# Flight_control_Prototipe.net
KiCad netlist of a schematic drawn in EAGLE
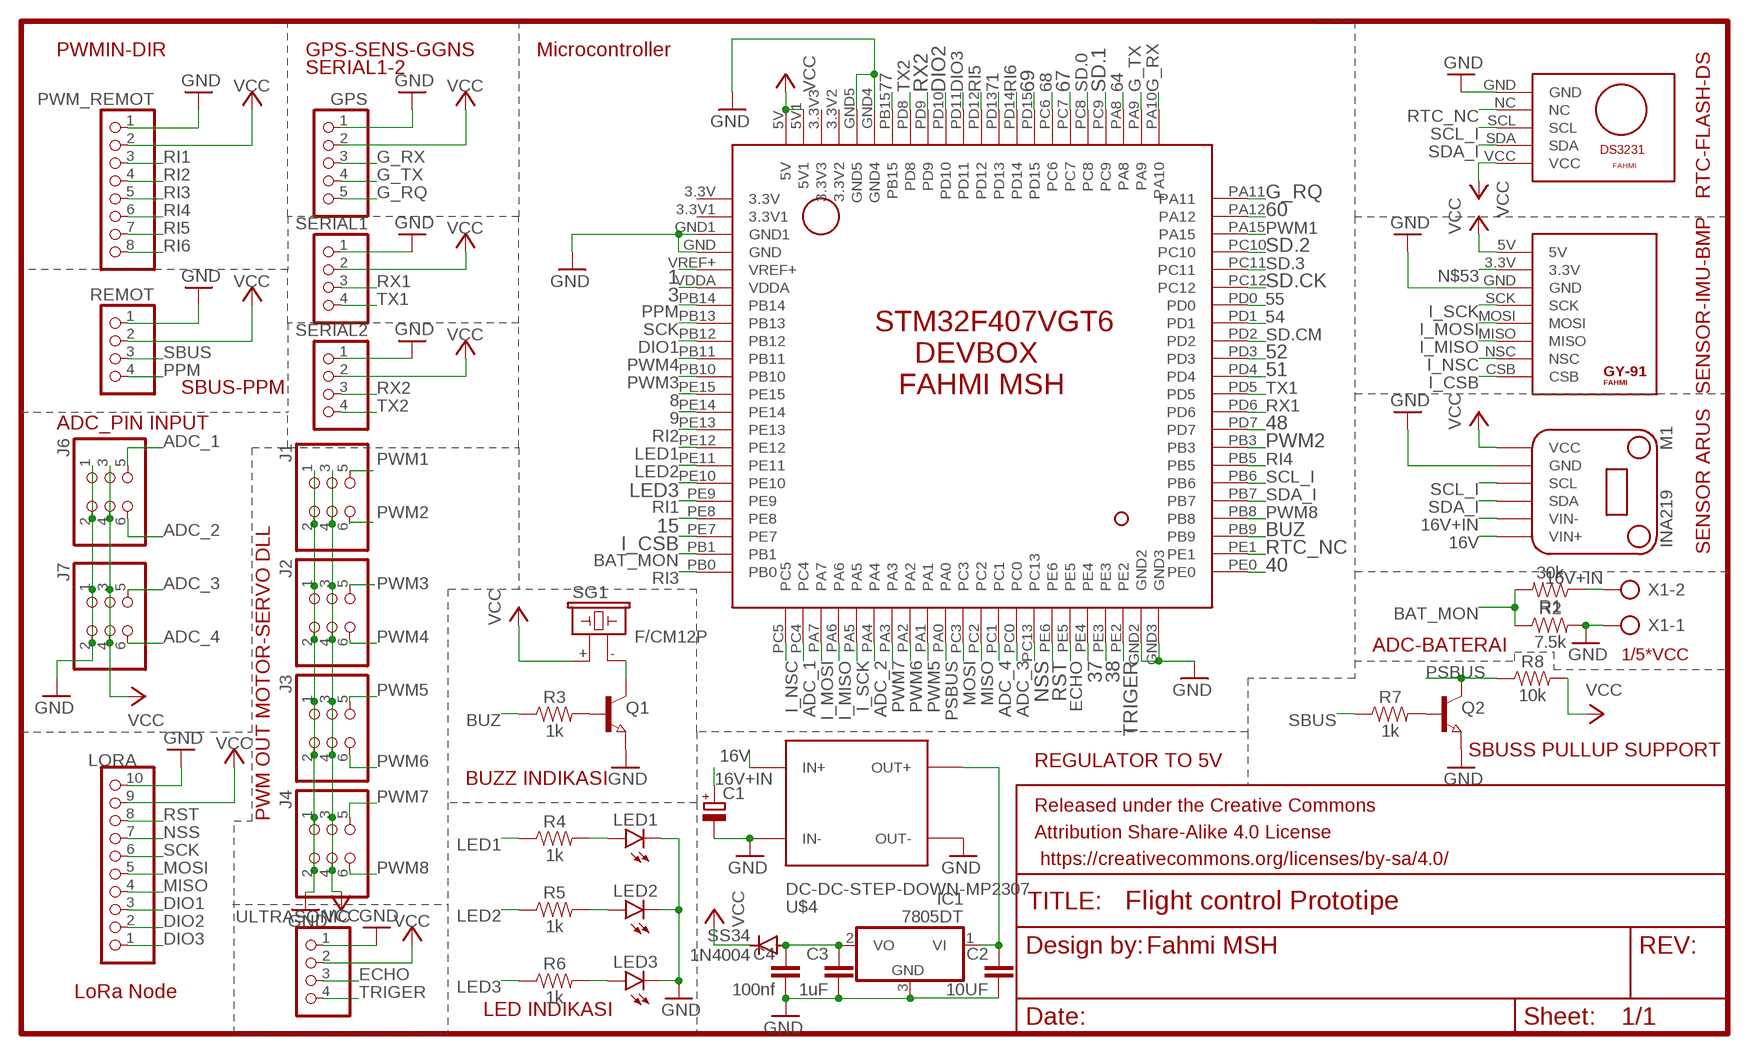
[diagram p0: schematic, sheet 1]

(export (version "E")
  (design (tool "Eeschema 10.0.6"))
  (components
    (comp (ref "C1")
      (value "CPOL-EUE3.5-8")
      (footprint "eagle-import:E3,5-8")
      (libsource (lib "eagle-import") (part "CPOL-EUE3.5-8"))
    )
    (comp (ref "C2")
      (value "10UF")
      (footprint "eagle-import:C0805K")
      (libsource (lib "eagle-import") (part "C-EUC0805K"))
    )
    (comp (ref "C3")
      (value "1uF")
      (footprint "eagle-import:C0805K")
      (libsource (lib "eagle-import") (part "C-EUC0805K"))
    )
    (comp (ref "C4")
      (value "100nf")
      (footprint "eagle-import:C0805K")
      (libsource (lib "eagle-import") (part "C-EUC0805K"))
    )
    (comp (ref "FRAME1")
      (value "FRAME-LEDGER")
      (footprint "eagle-import:CREATIVE_COMMONS")
      (libsource (lib "eagle-import") (part "FRAME-LEDGER"))
    )
    (comp (ref "GPS")
      (value "PINHD-1X5")
      (footprint "eagle-import:1X05")
      (libsource (lib "eagle-import") (part "PINHD-1X5"))
    )
    (comp (ref "IC1")
      (value "7805DT")
      (footprint "eagle-import:TO252")
      (libsource (lib "eagle-import") (part "78DT05"))
    )
    (comp (ref "J1")
      (value "PINHD-2X3")
      (footprint "eagle-import:2X03")
      (libsource (lib "eagle-import") (part "PINHD-2X3"))
    )
    (comp (ref "J2")
      (value "PINHD-2X3")
      (footprint "eagle-import:2X03")
      (libsource (lib "eagle-import") (part "PINHD-2X3"))
    )
    (comp (ref "J3")
      (value "PINHD-2X3")
      (footprint "eagle-import:2X03")
      (libsource (lib "eagle-import") (part "PINHD-2X3"))
    )
    (comp (ref "J4")
      (value "PINHD-2X3")
      (footprint "eagle-import:2X03")
      (libsource (lib "eagle-import") (part "PINHD-2X3"))
    )
    (comp (ref "J6")
      (value "PINHD-2X3")
      (footprint "eagle-import:2X03")
      (libsource (lib "eagle-import") (part "PINHD-2X3"))
    )
    (comp (ref "J7")
      (value "PINHD-2X3")
      (footprint "eagle-import:2X03")
      (libsource (lib "eagle-import") (part "PINHD-2X3"))
    )
    (comp (ref "LED1")
      (value "LED3MM")
      (footprint "eagle-import:LED3MM")
      (libsource (lib "eagle-import") (part "LED3MM"))
    )
    (comp (ref "LED2")
      (value "LED3MM")
      (footprint "eagle-import:LED3MM")
      (libsource (lib "eagle-import") (part "LED3MM"))
    )
    (comp (ref "LED3")
      (value "LED3MM")
      (footprint "eagle-import:LED3MM")
      (libsource (lib "eagle-import") (part "LED3MM"))
    )
    (comp (ref "LORA")
      (value "PINHD-1X10")
      (footprint "eagle-import:1X10")
      (libsource (lib "eagle-import") (part "PINHD-1X10"))
    )
    (comp (ref "M1")
      (value "INA219")
      (footprint "eagle-import:INA219")
      (libsource (lib "eagle-import") (part "INA219"))
    )
    (comp (ref "PWM_REMOT")
      (value "PINHD-1X8")
      (footprint "eagle-import:1X08")
      (libsource (lib "eagle-import") (part "PINHD-1X8"))
    )
    (comp (ref "Q1")
      (value "NPN-TRANSISTOR_SOT23")
      (footprint "eagle-import:SOT23")
      (libsource (lib "eagle-import") (part "NPN-TRANSISTOR_SOT23"))
    )
    (comp (ref "Q2")
      (value "NPN-TRANSISTOR_SOT23")
      (footprint "eagle-import:SOT23")
      (libsource (lib "eagle-import") (part "NPN-TRANSISTOR_SOT23"))
    )
    (comp (ref "R1")
      (value "30k")
      (footprint "eagle-import:0805")
      (libsource (lib "eagle-import") (part "0.75OHM-0805-1/4W-1%"))
    )
    (comp (ref "R2")
      (value "7.5k")
      (footprint "eagle-import:0805")
      (libsource (lib "eagle-import") (part "0.75OHM-0805-1/4W-1%"))
    )
    (comp (ref "R3")
      (value "1k")
      (footprint "eagle-import:0805")
      (libsource (lib "eagle-import") (part "0.75OHM-0805-1/4W-1%"))
    )
    (comp (ref "R4")
      (value "1k")
      (footprint "eagle-import:0805")
      (libsource (lib "eagle-import") (part "0.75OHM-0805-1/4W-1%"))
    )
    (comp (ref "R5")
      (value "1k")
      (footprint "eagle-import:0805")
      (libsource (lib "eagle-import") (part "0.75OHM-0805-1/4W-1%"))
    )
    (comp (ref "R6")
      (value "1k")
      (footprint "eagle-import:0805")
      (libsource (lib "eagle-import") (part "0.75OHM-0805-1/4W-1%"))
    )
    (comp (ref "R7")
      (value "1k")
      (footprint "eagle-import:0805")
      (libsource (lib "eagle-import") (part "0.75OHM-0805-1/4W-1%"))
    )
    (comp (ref "R8")
      (value "10k")
      (footprint "eagle-import:0805")
      (libsource (lib "eagle-import") (part "0.75OHM-0805-1/4W-1%"))
    )
    (comp (ref "REMOT")
      (value "PINHD-1X4")
      (footprint "eagle-import:1X04")
      (libsource (lib "eagle-import") (part "PINHD-1X4"))
    )
    (comp (ref "SERIAL1")
      (value "PINHD-1X4")
      (footprint "eagle-import:1X04")
      (libsource (lib "eagle-import") (part "PINHD-1X4"))
    )
    (comp (ref "SERIAL2")
      (value "PINHD-1X4")
      (footprint "eagle-import:1X04")
      (libsource (lib "eagle-import") (part "PINHD-1X4"))
    )
    (comp (ref "SG1")
      (value "F/CM12P")
      (footprint "eagle-import:F_CM12P")
      (libsource (lib "eagle-import") (part "F/CM12P"))
    )
    (comp (ref "SS34")
      (value "1N4004")
      (footprint "eagle-import:DO41-10")
      (libsource (lib "eagle-import") (part "1N4004"))
    )
    (comp (ref "U$1")
      (value "STM32F4DEVBOX")
      (footprint "eagle-import:STM32F4DEVBOX")
      (libsource (lib "eagle-import") (part "STM32F4DEVBOX"))
    )
    (comp (ref "U$2")
      (value "GY-91")
      (footprint "eagle-import:GY-91")
      (libsource (lib "eagle-import") (part "GY-91"))
    )
    (comp (ref "U$3")
      (value "DS3231MINI")
      (footprint "eagle-import:DS3231MINI")
      (libsource (lib "eagle-import") (part "DS3231MINI"))
    )
    (comp (ref "U$4")
      (value "DC-DC-STEP-DOWN-MP2307")
      (footprint "eagle-import:DC-DC-STEP-DOWN-MP2307")
      (libsource (lib "eagle-import") (part "DC-DC-STEP-DOWN-MP2307"))
    )
    (comp (ref "ULTRASONIC")
      (value "PINHD-1X4")
      (footprint "eagle-import:1X04")
      (libsource (lib "eagle-import") (part "PINHD-1X4"))
    )
    (comp (ref "X1")
      (value "AK500/2")
      (footprint "eagle-import:AK500_2")
      (libsource (lib "eagle-import") (part "AK500/2"))
    )
  )
  (nets
    (net (code "1") (name "/1") (class "Default")
      (node (ref "U$1") (pin "VREF+") (pinfunction "VREF+_VREF+") (pintype "bidirectional"))
    )
    (net (code "2") (name "/3") (class "Default")
      (node (ref "U$1") (pin "VDDA") (pinfunction "VDDA_VDDA") (pintype "bidirectional"))
    )
    (net (code "3") (name "/8") (class "Default")
      (node (ref "U$1") (pin "PE15") (pinfunction "PE15_PE15") (pintype "bidirectional"))
    )
    (net (code "4") (name "/9") (class "Default")
      (node (ref "U$1") (pin "PE14") (pinfunction "PE14_PE14") (pintype "bidirectional"))
    )
    (net (code "5") (name "/15") (class "Default")
      (node (ref "U$1") (pin "PE8") (pinfunction "PE8_PE8") (pintype "bidirectional"))
    )
    (net (code "6") (name "/16V") (class "Default")
      (node (ref "M1") (pin "VIN+") (pinfunction "VIN+_VIN+") (pintype "bidirectional"))
      (node (ref "U$4") (pin "IN+") (pinfunction "IN+_IN+") (pintype "bidirectional"))
    )
    (net (code "7") (name "/16V+IN") (class "Default")
      (node (ref "C1") (pin "+") (pinfunction "+_+") (pintype "passive"))
      (node (ref "M1") (pin "VIN-") (pinfunction "VIN-_VIN-") (pintype "bidirectional"))
      (node (ref "R1") (pin "1") (pinfunction "1_1") (pintype "passive"))
      (node (ref "X1") (pin "2") (pinfunction "KL_2") (pintype "passive"))
    )
    (net (code "8") (name "/37") (class "Default")
      (node (ref "U$1") (pin "PE4") (pinfunction "PE4_PE4") (pintype "bidirectional"))
    )
    (net (code "9") (name "/38") (class "Default")
      (node (ref "U$1") (pin "PE3") (pinfunction "PE3_PE3") (pintype "bidirectional"))
    )
    (net (code "10") (name "/40") (class "Default")
      (node (ref "U$1") (pin "PE0") (pinfunction "PE0_PE0") (pintype "bidirectional"))
    )
    (net (code "11") (name "/48") (class "Default")
      (node (ref "U$1") (pin "PD7") (pinfunction "PD7_PD7") (pintype "bidirectional"))
    )
    (net (code "12") (name "/51") (class "Default")
      (node (ref "U$1") (pin "PD4") (pinfunction "PD4_PD4") (pintype "bidirectional"))
    )
    (net (code "13") (name "/52") (class "Default")
      (node (ref "U$1") (pin "PD3") (pinfunction "PD3_PD3") (pintype "bidirectional"))
    )
    (net (code "14") (name "/54") (class "Default")
      (node (ref "U$1") (pin "PD1") (pinfunction "PD1_PD1") (pintype "bidirectional"))
    )
    (net (code "15") (name "/55") (class "Default")
      (node (ref "U$1") (pin "PD0") (pinfunction "PD0_PD0") (pintype "bidirectional"))
    )
    (net (code "16") (name "/60") (class "Default")
      (node (ref "U$1") (pin "PA12") (pinfunction "PA12_PA12") (pintype "bidirectional"))
    )
    (net (code "17") (name "/64") (class "Default")
      (node (ref "U$1") (pin "PA8") (pinfunction "PA8_PA8") (pintype "bidirectional"))
    )
    (net (code "18") (name "/67") (class "Default")
      (node (ref "U$1") (pin "PC7") (pinfunction "PC7_PC7") (pintype "bidirectional"))
    )
    (net (code "19") (name "/68") (class "Default")
      (node (ref "U$1") (pin "PC6") (pinfunction "PC6_PC6") (pintype "bidirectional"))
    )
    (net (code "20") (name "/69") (class "Default")
      (node (ref "U$1") (pin "PD15") (pinfunction "PD15_PD15") (pintype "bidirectional"))
    )
    (net (code "21") (name "/71") (class "Default")
      (node (ref "U$1") (pin "PD13") (pinfunction "PD13_PD13") (pintype "bidirectional"))
    )
    (net (code "22") (name "/77") (class "Default")
      (node (ref "U$1") (pin "PB15") (pinfunction "PB15_PB15") (pintype "bidirectional"))
    )
    (net (code "23") (name "/ADC_1") (class "Default")
      (node (ref "J6") (pin "5") (pinfunction "5_5") (pintype "passive"))
      (node (ref "U$1") (pin "PC4") (pinfunction "PC4_PC4") (pintype "bidirectional"))
    )
    (net (code "24") (name "/ADC_2") (class "Default")
      (node (ref "J6") (pin "6") (pinfunction "6_6") (pintype "passive"))
      (node (ref "U$1") (pin "PA4") (pinfunction "PA4_PA4") (pintype "bidirectional"))
    )
    (net (code "25") (name "/ADC_3") (class "Default")
      (node (ref "J7") (pin "5") (pinfunction "5_5") (pintype "passive"))
      (node (ref "U$1") (pin "PC0") (pinfunction "PC0_PC0") (pintype "bidirectional"))
    )
    (net (code "26") (name "/ADC_4") (class "Default")
      (node (ref "J7") (pin "6") (pinfunction "6_6") (pintype "passive"))
      (node (ref "U$1") (pin "PC1") (pinfunction "PC1_PC1") (pintype "bidirectional"))
    )
    (net (code "27") (name "/BAT_MON") (class "Default")
      (node (ref "R1") (pin "2") (pinfunction "2_2") (pintype "passive"))
      (node (ref "R2") (pin "1") (pinfunction "1_1") (pintype "passive"))
      (node (ref "U$1") (pin "PB1") (pinfunction "PB1_PB1") (pintype "bidirectional"))
    )
    (net (code "28") (name "/BUZ") (class "Default")
      (node (ref "R3") (pin "1") (pinfunction "1_1") (pintype "passive"))
      (node (ref "U$1") (pin "PB9") (pinfunction "PB9_PB9") (pintype "bidirectional"))
    )
    (net (code "29") (name "/DIO1") (class "Default")
      (node (ref "LORA") (pin "3") (pinfunction "3_3") (pintype "passive"))
      (node (ref "U$1") (pin "PB12") (pinfunction "PB12_PB12") (pintype "bidirectional"))
    )
    (net (code "30") (name "/DIO2") (class "Default")
      (node (ref "LORA") (pin "2") (pinfunction "2_2") (pintype "passive"))
      (node (ref "U$1") (pin "PD10") (pinfunction "PD10_PD10") (pintype "bidirectional"))
    )
    (net (code "31") (name "/DIO3") (class "Default")
      (node (ref "LORA") (pin "1") (pinfunction "1_1") (pintype "passive"))
      (node (ref "U$1") (pin "PD11") (pinfunction "PD11_PD11") (pintype "bidirectional"))
    )
    (net (code "32") (name "/ECHO") (class "Default")
      (node (ref "U$1") (pin "PE5") (pinfunction "PE5_PE5") (pintype "bidirectional"))
      (node (ref "ULTRASONIC") (pin "3") (pinfunction "3_3") (pintype "passive"))
    )
    (net (code "33") (name "/G_RQ") (class "Default")
      (node (ref "GPS") (pin "5") (pinfunction "5_5") (pintype "passive"))
      (node (ref "U$1") (pin "PA11") (pinfunction "PA11_PA11") (pintype "bidirectional"))
    )
    (net (code "34") (name "/G_RX") (class "Default")
      (node (ref "GPS") (pin "3") (pinfunction "3_3") (pintype "passive"))
      (node (ref "U$1") (pin "PA10") (pinfunction "PA10_PA10") (pintype "bidirectional"))
    )
    (net (code "35") (name "/G_TX") (class "Default")
      (node (ref "GPS") (pin "4") (pinfunction "4_4") (pintype "passive"))
      (node (ref "U$1") (pin "PA9") (pinfunction "PA9_PA9") (pintype "bidirectional"))
    )
    (net (code "36") (name "/I_CSB") (class "Default")
      (node (ref "U$1") (pin "PE7") (pinfunction "PE7_PE7") (pintype "bidirectional"))
      (node (ref "U$2") (pin "CSB") (pinfunction "CSB_CSB") (pintype "bidirectional"))
    )
    (net (code "37") (name "/I_MISO") (class "Default")
      (node (ref "U$1") (pin "PA6") (pinfunction "PA6_PA6") (pintype "bidirectional"))
      (node (ref "U$2") (pin "MISO") (pinfunction "MISO_MISO") (pintype "bidirectional"))
    )
    (net (code "38") (name "/I_MOSI") (class "Default")
      (node (ref "U$1") (pin "PA7") (pinfunction "PA7_PA7") (pintype "bidirectional"))
      (node (ref "U$2") (pin "MOSI") (pinfunction "MOSI_MOSI") (pintype "bidirectional"))
    )
    (net (code "39") (name "/I_NSC") (class "Default")
      (node (ref "U$1") (pin "PC5") (pinfunction "PC5_PC5") (pintype "bidirectional"))
      (node (ref "U$2") (pin "NSC") (pinfunction "NSC_NSC") (pintype "bidirectional"))
    )
    (net (code "40") (name "/I_SCK") (class "Default")
      (node (ref "U$1") (pin "PA5") (pinfunction "PA5_PA5") (pintype "bidirectional"))
      (node (ref "U$2") (pin "SCK") (pinfunction "SCK_SCK") (pintype "bidirectional"))
    )
    (net (code "41") (name "/LED1") (class "Default")
      (node (ref "R4") (pin "1") (pinfunction "1_1") (pintype "passive"))
      (node (ref "U$1") (pin "PE12") (pinfunction "PE12_PE12") (pintype "bidirectional"))
    )
    (net (code "42") (name "/LED2") (class "Default")
      (node (ref "R5") (pin "1") (pinfunction "1_1") (pintype "passive"))
      (node (ref "U$1") (pin "PE11") (pinfunction "PE11_PE11") (pintype "bidirectional"))
    )
    (net (code "43") (name "/LED3") (class "Default")
      (node (ref "R6") (pin "1") (pinfunction "1_1") (pintype "passive"))
      (node (ref "U$1") (pin "PE10") (pinfunction "PE10_PE10") (pintype "bidirectional"))
    )
    (net (code "44") (name "/MISO") (class "Default")
      (node (ref "LORA") (pin "4") (pinfunction "4_4") (pintype "passive"))
      (node (ref "U$1") (pin "PC2") (pinfunction "PC2_PC2") (pintype "bidirectional"))
    )
    (net (code "45") (name "/MOSI") (class "Default")
      (node (ref "LORA") (pin "5") (pinfunction "5_5") (pintype "passive"))
      (node (ref "U$1") (pin "PC3") (pinfunction "PC3_PC3") (pintype "bidirectional"))
    )
    (net (code "46") (name "/N$53") (class "Default")
      (node (ref "U$2") (pin "3.3V") (pinfunction "3.3V_3.3V") (pintype "bidirectional"))
    )
    (net (code "47") (name "/NSS") (class "Default")
      (node (ref "LORA") (pin "7") (pinfunction "7_7") (pintype "passive"))
      (node (ref "U$1") (pin "PC13") (pinfunction "PC13_PC13") (pintype "bidirectional"))
    )
    (net (code "48") (name "/PPM") (class "Default")
      (node (ref "REMOT") (pin "4") (pinfunction "4_4") (pintype "passive"))
      (node (ref "U$1") (pin "PB14") (pinfunction "PB14_PB14") (pintype "bidirectional"))
    )
    (net (code "49") (name "/PSBUS") (class "Default")
      (node (ref "Q2") (pin "3") (pinfunction "C_3") (pintype "passive"))
      (node (ref "R8") (pin "1") (pinfunction "1_1") (pintype "passive"))
      (node (ref "U$1") (pin "PA0") (pinfunction "PA0_PA0") (pintype "bidirectional"))
    )
    (net (code "50") (name "/PWM1") (class "Default")
      (node (ref "J1") (pin "5") (pinfunction "5_5") (pintype "passive"))
      (node (ref "U$1") (pin "PA15") (pinfunction "PA15_PA15") (pintype "bidirectional"))
    )
    (net (code "51") (name "/PWM2") (class "Default")
      (node (ref "J1") (pin "6") (pinfunction "6_6") (pintype "passive"))
      (node (ref "U$1") (pin "PB3") (pinfunction "PB3_PB3") (pintype "bidirectional"))
    )
    (net (code "52") (name "/PWM3") (class "Default")
      (node (ref "J2") (pin "5") (pinfunction "5_5") (pintype "passive"))
      (node (ref "U$1") (pin "PB10") (pinfunction "PB10_PB10") (pintype "bidirectional"))
    )
    (net (code "53") (name "/PWM4") (class "Default")
      (node (ref "J2") (pin "6") (pinfunction "6_6") (pintype "passive"))
      (node (ref "U$1") (pin "PB11") (pinfunction "PB11_PB11") (pintype "bidirectional"))
    )
    (net (code "54") (name "/PWM5") (class "Default")
      (node (ref "J3") (pin "5") (pinfunction "5_5") (pintype "passive"))
      (node (ref "U$1") (pin "PA1") (pinfunction "PA1_PA1") (pintype "bidirectional"))
    )
    (net (code "55") (name "/PWM6") (class "Default")
      (node (ref "J3") (pin "6") (pinfunction "6_6") (pintype "passive"))
      (node (ref "U$1") (pin "PA2") (pinfunction "PA2_PA2") (pintype "bidirectional"))
    )
    (net (code "56") (name "/PWM7") (class "Default")
      (node (ref "J4") (pin "5") (pinfunction "5_5") (pintype "passive"))
      (node (ref "U$1") (pin "PA3") (pinfunction "PA3_PA3") (pintype "bidirectional"))
    )
    (net (code "57") (name "/PWM8") (class "Default")
      (node (ref "J4") (pin "6") (pinfunction "6_6") (pintype "passive"))
      (node (ref "U$1") (pin "PB8") (pinfunction "PB8_PB8") (pintype "bidirectional"))
    )
    (net (code "58") (name "/RI1") (class "Default")
      (node (ref "PWM_REMOT") (pin "3") (pinfunction "3_3") (pintype "passive"))
      (node (ref "U$1") (pin "PE9") (pinfunction "PE9_PE9") (pintype "bidirectional"))
    )
    (net (code "59") (name "/RI2") (class "Default")
      (node (ref "PWM_REMOT") (pin "4") (pinfunction "4_4") (pintype "passive"))
      (node (ref "U$1") (pin "PE13") (pinfunction "PE13_PE13") (pintype "bidirectional"))
    )
    (net (code "60") (name "/RI3") (class "Default")
      (node (ref "PWM_REMOT") (pin "5") (pinfunction "5_5") (pintype "passive"))
      (node (ref "U$1") (pin "PB0") (pinfunction "PB0_PB0") (pintype "bidirectional"))
    )
    (net (code "61") (name "/RI4") (class "Default")
      (node (ref "PWM_REMOT") (pin "6") (pinfunction "6_6") (pintype "passive"))
      (node (ref "U$1") (pin "PB5") (pinfunction "PB5_PB5") (pintype "bidirectional"))
    )
    (net (code "62") (name "/RI5") (class "Default")
      (node (ref "PWM_REMOT") (pin "7") (pinfunction "7_7") (pintype "passive"))
      (node (ref "U$1") (pin "PD12") (pinfunction "PD12_PD12") (pintype "bidirectional"))
    )
    (net (code "63") (name "/RI6") (class "Default")
      (node (ref "PWM_REMOT") (pin "8") (pinfunction "8_8") (pintype "passive"))
      (node (ref "U$1") (pin "PD14") (pinfunction "PD14_PD14") (pintype "bidirectional"))
    )
    (net (code "64") (name "/RST") (class "Default")
      (node (ref "LORA") (pin "8") (pinfunction "8_8") (pintype "passive"))
      (node (ref "U$1") (pin "PE6") (pinfunction "PE6_PE6") (pintype "bidirectional"))
    )
    (net (code "65") (name "/RTC_NC") (class "Default")
      (node (ref "U$1") (pin "PE1") (pinfunction "PE1_PE1") (pintype "bidirectional"))
      (node (ref "U$3") (pin "NC") (pinfunction "NC_NC") (pintype "bidirectional"))
    )
    (net (code "66") (name "/RX1") (class "Default")
      (node (ref "SERIAL1") (pin "3") (pinfunction "3_3") (pintype "passive"))
      (node (ref "U$1") (pin "PD6") (pinfunction "PD6_PD6") (pintype "bidirectional"))
    )
    (net (code "67") (name "/RX2") (class "Default")
      (node (ref "SERIAL2") (pin "3") (pinfunction "3_3") (pintype "passive"))
      (node (ref "U$1") (pin "PD9") (pinfunction "PD9_PD9") (pintype "bidirectional"))
    )
    (net (code "68") (name "/SBUS") (class "Default")
      (node (ref "R7") (pin "1") (pinfunction "1_1") (pintype "passive"))
      (node (ref "REMOT") (pin "3") (pinfunction "3_3") (pintype "passive"))
    )
    (net (code "69") (name "/SCK") (class "Default")
      (node (ref "LORA") (pin "6") (pinfunction "6_6") (pintype "passive"))
      (node (ref "U$1") (pin "PB13") (pinfunction "PB13_PB13") (pintype "bidirectional"))
    )
    (net (code "70") (name "/SCL_I") (class "Default")
      (node (ref "M1") (pin "SCL") (pinfunction "SCL_SCL") (pintype "bidirectional"))
      (node (ref "U$1") (pin "PB6") (pinfunction "PB6_PB6") (pintype "bidirectional"))
      (node (ref "U$3") (pin "SCL") (pinfunction "SCL_SCL") (pintype "bidirectional"))
    )
    (net (code "71") (name "/SD.0") (class "Default")
      (node (ref "U$1") (pin "PC8") (pinfunction "PC8_PC8") (pintype "bidirectional"))
    )
    (net (code "72") (name "/SD.1") (class "Default")
      (node (ref "U$1") (pin "PC9") (pinfunction "PC9_PC9") (pintype "bidirectional"))
    )
    (net (code "73") (name "/SD.2") (class "Default")
      (node (ref "U$1") (pin "PC10") (pinfunction "PC10_PC10") (pintype "bidirectional"))
    )
    (net (code "74") (name "/SD.3") (class "Default")
      (node (ref "U$1") (pin "PC11") (pinfunction "PC11_PC11") (pintype "bidirectional"))
    )
    (net (code "75") (name "/SD.CK") (class "Default")
      (node (ref "U$1") (pin "PC12") (pinfunction "PC12_PC12") (pintype "bidirectional"))
    )
    (net (code "76") (name "/SD.CM") (class "Default")
      (node (ref "U$1") (pin "PD2") (pinfunction "PD2_PD2") (pintype "bidirectional"))
    )
    (net (code "77") (name "/SDA_I") (class "Default")
      (node (ref "M1") (pin "SDA") (pinfunction "SDA_SDA") (pintype "bidirectional"))
      (node (ref "U$1") (pin "PB7") (pinfunction "PB7_PB7") (pintype "bidirectional"))
      (node (ref "U$3") (pin "SDA") (pinfunction "SDA_SDA") (pintype "bidirectional"))
    )
    (net (code "78") (name "/TRIGER") (class "Default")
      (node (ref "U$1") (pin "PE2") (pinfunction "PE2_PE2") (pintype "bidirectional"))
      (node (ref "ULTRASONIC") (pin "4") (pinfunction "4_4") (pintype "passive"))
    )
    (net (code "79") (name "/TX1") (class "Default")
      (node (ref "SERIAL1") (pin "4") (pinfunction "4_4") (pintype "passive"))
      (node (ref "U$1") (pin "PD5") (pinfunction "PD5_PD5") (pintype "bidirectional"))
    )
    (net (code "80") (name "/TX2") (class "Default")
      (node (ref "SERIAL2") (pin "4") (pinfunction "4_4") (pintype "passive"))
      (node (ref "U$1") (pin "PD8") (pinfunction "PD8_PD8") (pintype "bidirectional"))
    )
    (net (code "81") (name "GND") (class "Default")
      (node (ref "C1") (pin "-") (pinfunction "-_-") (pintype "passive"))
      (node (ref "C2") (pin "2") (pinfunction "2_2") (pintype "passive"))
      (node (ref "C3") (pin "2") (pinfunction "2_2") (pintype "passive"))
      (node (ref "C4") (pin "2") (pinfunction "2_2") (pintype "passive"))
      (node (ref "GPS") (pin "1") (pinfunction "1_1") (pintype "passive"))
      (node (ref "IC1") (pin "3") (pinfunction "GND_3") (pintype "passive"))
      (node (ref "J1") (pin "1") (pinfunction "1_1") (pintype "passive"))
      (node (ref "J1") (pin "2") (pinfunction "2_2") (pintype "passive"))
      (node (ref "J2") (pin "1") (pinfunction "1_1") (pintype "passive"))
      (node (ref "J2") (pin "2") (pinfunction "2_2") (pintype "passive"))
      (node (ref "J3") (pin "1") (pinfunction "1_1") (pintype "passive"))
      (node (ref "J3") (pin "2") (pinfunction "2_2") (pintype "passive"))
      (node (ref "J4") (pin "1") (pinfunction "1_1") (pintype "passive"))
      (node (ref "J4") (pin "2") (pinfunction "2_2") (pintype "passive"))
      (node (ref "J6") (pin "1") (pinfunction "1_1") (pintype "passive"))
      (node (ref "J6") (pin "2") (pinfunction "2_2") (pintype "passive"))
      (node (ref "J7") (pin "1") (pinfunction "1_1") (pintype "passive"))
      (node (ref "J7") (pin "2") (pinfunction "2_2") (pintype "passive"))
      (node (ref "LED1") (pin "K") (pinfunction "C_K") (pintype "passive"))
      (node (ref "LED2") (pin "K") (pinfunction "C_K") (pintype "passive"))
      (node (ref "LED3") (pin "K") (pinfunction "C_K") (pintype "passive"))
      (node (ref "LORA") (pin "10") (pinfunction "10_10") (pintype "passive"))
      (node (ref "M1") (pin "GND") (pinfunction "GND_GND") (pintype "bidirectional"))
      (node (ref "PWM_REMOT") (pin "1") (pinfunction "1_1") (pintype "passive"))
      (node (ref "Q1") (pin "2") (pinfunction "E_2") (pintype "passive"))
      (node (ref "Q2") (pin "2") (pinfunction "E_2") (pintype "passive"))
      (node (ref "R2") (pin "2") (pinfunction "2_2") (pintype "passive"))
      (node (ref "REMOT") (pin "1") (pinfunction "1_1") (pintype "passive"))
      (node (ref "SERIAL1") (pin "1") (pinfunction "1_1") (pintype "passive"))
      (node (ref "SERIAL2") (pin "1") (pinfunction "1_1") (pintype "passive"))
      (node (ref "U$1") (pin "GND") (pinfunction "GND_GND") (pintype "bidirectional"))
      (node (ref "U$1") (pin "GND1") (pinfunction "GND1_GND1") (pintype "bidirectional"))
      (node (ref "U$1") (pin "GND2") (pinfunction "GND2_GND2") (pintype "bidirectional"))
      (node (ref "U$1") (pin "GND3") (pinfunction "GND3_GND3") (pintype "bidirectional"))
      (node (ref "U$1") (pin "GND4") (pinfunction "GND4_GND4") (pintype "bidirectional"))
      (node (ref "U$1") (pin "GND5") (pinfunction "GND5_GND5") (pintype "bidirectional"))
      (node (ref "U$2") (pin "GND") (pinfunction "GND_GND") (pintype "bidirectional"))
      (node (ref "U$3") (pin "GND") (pinfunction "GND_GND") (pintype "bidirectional"))
      (node (ref "U$4") (pin "IN-") (pinfunction "IN-_IN-") (pintype "bidirectional"))
      (node (ref "U$4") (pin "OUT-") (pinfunction "OUT-_OUT-") (pintype "bidirectional"))
      (node (ref "ULTRASONIC") (pin "1") (pinfunction "1_1") (pintype "passive"))
      (node (ref "X1") (pin "1") (pinfunction "KL_1") (pintype "passive"))
    )
    (net (code "82") (name "Net-(IC1-VI)") (class "Default")
      (node (ref "C2") (pin "1") (pinfunction "1_1") (pintype "passive"))
      (node (ref "IC1") (pin "1") (pinfunction "VI_1") (pintype "input"))
      (node (ref "U$4") (pin "OUT+") (pinfunction "OUT+_OUT+") (pintype "bidirectional"))
    )
    (net (code "83") (name "Net-(IC1-VO)") (class "Default")
      (node (ref "C3") (pin "1") (pinfunction "1_1") (pintype "passive"))
      (node (ref "C4") (pin "1") (pinfunction "1_1") (pintype "passive"))
      (node (ref "IC1") (pin "2") (pinfunction "VO_2") (pintype "passive"))
      (node (ref "SS34") (pin "A") (pinfunction "A_A") (pintype "passive"))
    )
    (net (code "84") (name "Net-(LED1-PadA)") (class "Default")
      (node (ref "LED1") (pin "A") (pinfunction "A_A") (pintype "passive"))
      (node (ref "R4") (pin "2") (pinfunction "2_2") (pintype "passive"))
    )
    (net (code "85") (name "Net-(LED2-PadA)") (class "Default")
      (node (ref "LED2") (pin "A") (pinfunction "A_A") (pintype "passive"))
      (node (ref "R5") (pin "2") (pinfunction "2_2") (pintype "passive"))
    )
    (net (code "86") (name "Net-(LED3-PadA)") (class "Default")
      (node (ref "LED3") (pin "A") (pinfunction "A_A") (pintype "passive"))
      (node (ref "R6") (pin "2") (pinfunction "2_2") (pintype "passive"))
    )
    (net (code "87") (name "Net-(Q1-B)") (class "Default")
      (node (ref "Q1") (pin "1") (pinfunction "B_1") (pintype "passive"))
      (node (ref "R3") (pin "2") (pinfunction "2_2") (pintype "passive"))
    )
    (net (code "88") (name "Net-(Q1-C)") (class "Default")
      (node (ref "Q1") (pin "3") (pinfunction "C_3") (pintype "passive"))
      (node (ref "SG1") (pin "-") (pinfunction "2_-") (pintype "passive"))
    )
    (net (code "89") (name "Net-(Q2-B)") (class "Default")
      (node (ref "Q2") (pin "1") (pinfunction "B_1") (pintype "passive"))
      (node (ref "R7") (pin "2") (pinfunction "2_2") (pintype "passive"))
    )
    (net (code "90") (name "VCC") (class "Default")
      (node (ref "GPS") (pin "2") (pinfunction "2_2") (pintype "passive"))
      (node (ref "J1") (pin "3") (pinfunction "3_3") (pintype "passive"))
      (node (ref "J1") (pin "4") (pinfunction "4_4") (pintype "passive"))
      (node (ref "J2") (pin "3") (pinfunction "3_3") (pintype "passive"))
      (node (ref "J2") (pin "4") (pinfunction "4_4") (pintype "passive"))
      (node (ref "J3") (pin "3") (pinfunction "3_3") (pintype "passive"))
      (node (ref "J3") (pin "4") (pinfunction "4_4") (pintype "passive"))
      (node (ref "J4") (pin "3") (pinfunction "3_3") (pintype "passive"))
      (node (ref "J4") (pin "4") (pinfunction "4_4") (pintype "passive"))
      (node (ref "J6") (pin "3") (pinfunction "3_3") (pintype "passive"))
      (node (ref "J6") (pin "4") (pinfunction "4_4") (pintype "passive"))
      (node (ref "J7") (pin "3") (pinfunction "3_3") (pintype "passive"))
      (node (ref "J7") (pin "4") (pinfunction "4_4") (pintype "passive"))
      (node (ref "LORA") (pin "9") (pinfunction "9_9") (pintype "passive"))
      (node (ref "M1") (pin "VCC") (pinfunction "VCC_VCC") (pintype "bidirectional"))
      (node (ref "PWM_REMOT") (pin "2") (pinfunction "2_2") (pintype "passive"))
      (node (ref "R8") (pin "2") (pinfunction "2_2") (pintype "passive"))
      (node (ref "REMOT") (pin "2") (pinfunction "2_2") (pintype "passive"))
      (node (ref "SERIAL1") (pin "2") (pinfunction "2_2") (pintype "passive"))
      (node (ref "SERIAL2") (pin "2") (pinfunction "2_2") (pintype "passive"))
      (node (ref "SG1") (pin "+") (pinfunction "1_+") (pintype "passive"))
      (node (ref "SS34") (pin "C") (pinfunction "C_C") (pintype "passive"))
      (node (ref "U$1") (pin "5V") (pinfunction "5V_5V") (pintype "bidirectional"))
      (node (ref "U$1") (pin "5V1") (pinfunction "5V1_5V1") (pintype "bidirectional"))
      (node (ref "U$2") (pin "5V") (pinfunction "5V_5V") (pintype "bidirectional"))
      (node (ref "U$3") (pin "VCC") (pinfunction "VCC_VCC") (pintype "bidirectional"))
      (node (ref "ULTRASONIC") (pin "2") (pinfunction "2_2") (pintype "passive"))
    )
    (net (code "91") (name "unconnected-(U$1-Pad3.3V)") (class "Default")
      (node (ref "U$1") (pin "3.3V") (pinfunction "3.3V_3.3V") (pintype "bidirectional"))
    )
    (net (code "92") (name "unconnected-(U$1-Pad3.3V1)") (class "Default")
      (node (ref "U$1") (pin "3.3V1") (pinfunction "3.3V1_3.3V1") (pintype "bidirectional"))
    )
    (net (code "93") (name "unconnected-(U$1-Pad3.3V2)") (class "Default")
      (node (ref "U$1") (pin "3.3V2") (pinfunction "3.3V2_3.3V2") (pintype "bidirectional"))
    )
    (net (code "94") (name "unconnected-(U$1-Pad3.3V3)") (class "Default")
      (node (ref "U$1") (pin "3.3V3") (pinfunction "3.3V3_3.3V3") (pintype "bidirectional"))
    )
  )
)
